# Current_Sensor.net
KiCad netlist of a schematic drawn in Altium Designer
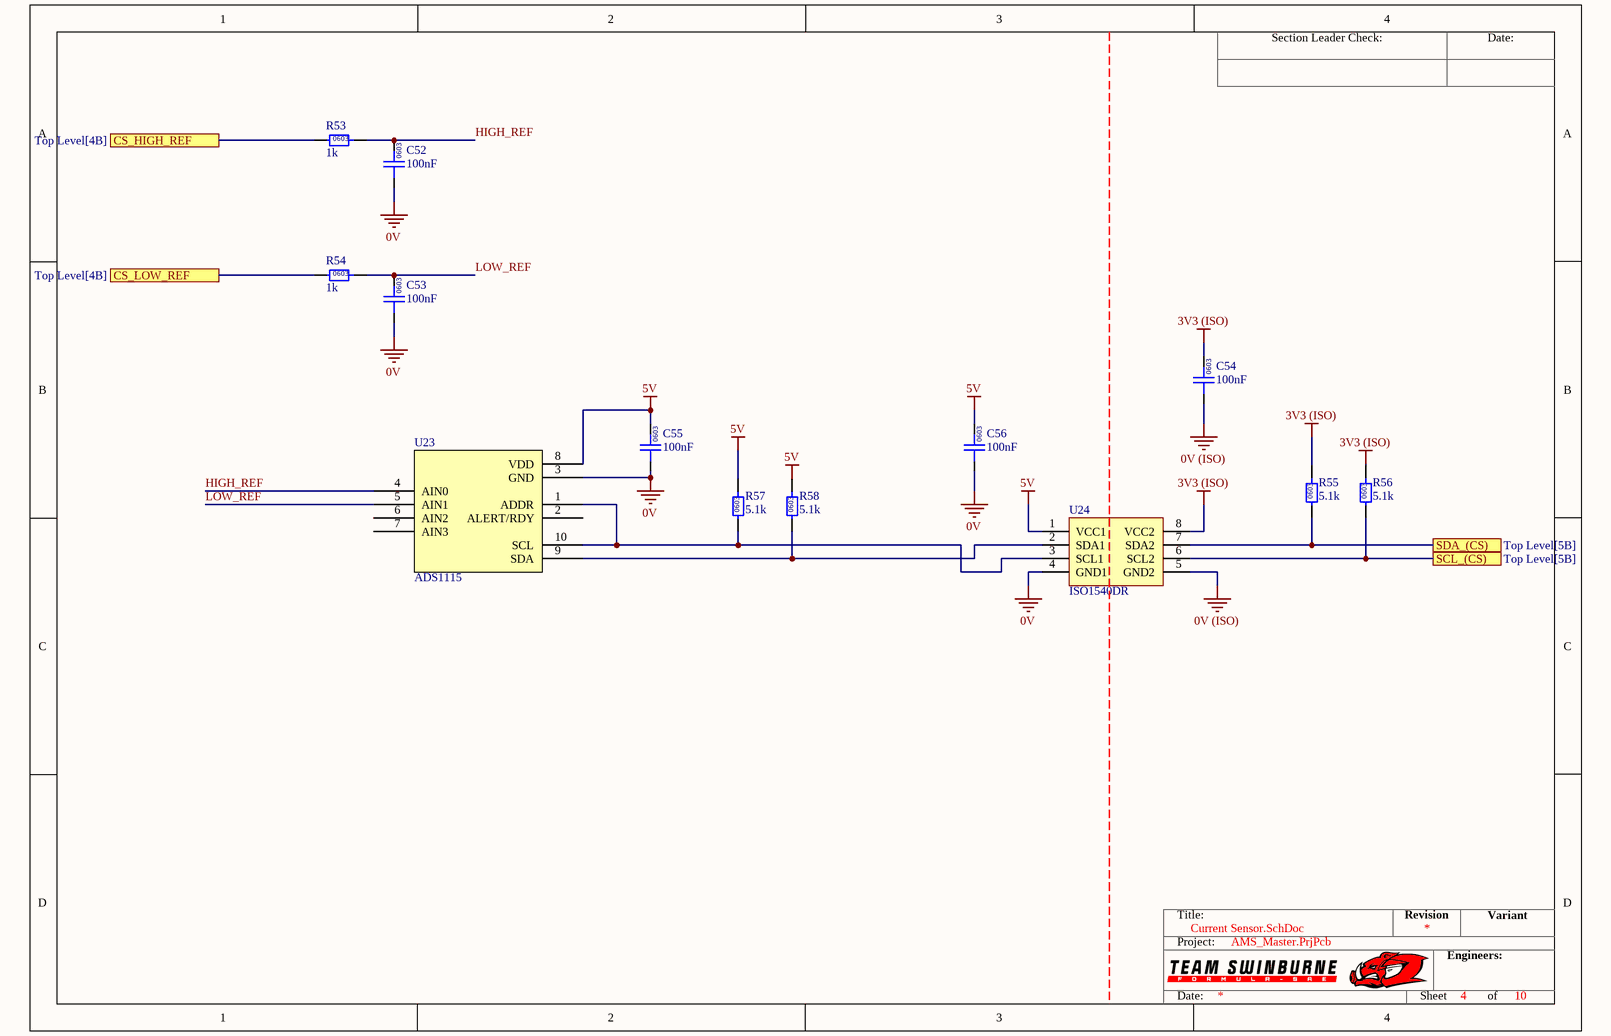
[diagram p0: Current Sensor.SchDoc]

(export (version "E")
  (design (tool "Eeschema 10.0.6"))
  (components
    (comp (ref "C52")
      (value "100nF")
      (footprint "0603")
      (fields
        (field (name "PART NUMBER") "GCM188L81H104KA57D")
        (field (name "MANUFACTURER") "muRata")
        (field (name "TOLERANCE") "±10%")
      )
      (libsource (lib "ts_standard_library") (part "Capacitor 0603"))
    )
    (comp (ref "C53")
      (value "100nF")
      (footprint "0603")
      (fields
        (field (name "PART NUMBER") "GCM188L81H104KA57D")
        (field (name "MANUFACTURER") "muRata")
        (field (name "TOLERANCE") "±10%")
      )
      (libsource (lib "ts_standard_library") (part "Capacitor 0603"))
    )
    (comp (ref "C54")
      (value "100nF")
      (footprint "0603")
      (fields
        (field (name "PART NUMBER") "GCM188L81H104KA57D")
        (field (name "MANUFACTURER") "muRata")
        (field (name "TOLERANCE") "±10%")
      )
      (libsource (lib "ts_standard_library") (part "Capacitor 0603"))
    )
    (comp (ref "C55")
      (value "100nF")
      (footprint "0603")
      (fields
        (field (name "PART NUMBER") "GCM188L81H104KA57D")
        (field (name "MANUFACTURER") "muRata")
        (field (name "TOLERANCE") "±10%")
      )
      (libsource (lib "ts_standard_library") (part "Capacitor 0603"))
    )
    (comp (ref "C56")
      (value "100nF")
      (footprint "0603")
      (fields
        (field (name "PART NUMBER") "GCM188L81H104KA57D")
        (field (name "MANUFACTURER") "muRata")
        (field (name "TOLERANCE") "±10%")
      )
      (libsource (lib "ts_standard_library") (part "Capacitor 0603"))
    )
    (comp (ref "R53")
      (value "1k")
      (footprint "0603")
      (fields
        (field (name "PART NUMBER") "RC0603FR-071KL")
        (field (name "MANUFACTURER") "YAGEO")
        (field (name "TOLERANCE") "0.01")
      )
      (libsource (lib "ts_standard_library") (part "Resistor 0603"))
    )
    (comp (ref "R54")
      (value "1k")
      (footprint "0603")
      (fields
        (field (name "PART NUMBER") "RC0603FR-071KL")
        (field (name "MANUFACTURER") "YAGEO")
        (field (name "TOLERANCE") "0.01")
      )
      (libsource (lib "ts_standard_library") (part "Resistor 0603"))
    )
    (comp (ref "R55")
      (value "5.1k")
      (footprint "0603")
      (fields
        (field (name "PART NUMBER") "RC0603JR-075K1L")
        (field (name "MANUFACTURER") "YAGEO")
        (field (name "TOLERANCE") "0.01")
      )
      (libsource (lib "ts_standard_library") (part "Resistor 0603"))
    )
    (comp (ref "R56")
      (value "5.1k")
      (footprint "0603")
      (fields
        (field (name "PART NUMBER") "RC0603JR-075K1L")
        (field (name "MANUFACTURER") "YAGEO")
        (field (name "TOLERANCE") "0.01")
      )
      (libsource (lib "ts_standard_library") (part "Resistor 0603"))
    )
    (comp (ref "R57")
      (value "5.1k")
      (footprint "0603")
      (fields
        (field (name "PART NUMBER") "RC0603JR-075K1L")
        (field (name "MANUFACTURER") "YAGEO")
        (field (name "TOLERANCE") "0.01")
      )
      (libsource (lib "ts_standard_library") (part "Resistor 0603"))
    )
    (comp (ref "R58")
      (value "5.1k")
      (footprint "0603")
      (fields
        (field (name "PART NUMBER") "RC0603JR-075K1L")
        (field (name "MANUFACTURER") "YAGEO")
        (field (name "TOLERANCE") "0.01")
      )
      (libsource (lib "ts_standard_library") (part "Resistor 0603"))
    )
    (comp (ref "U23")
      (value "ADS1115")
      (footprint "TI 10-VSSOP")
      (description "16 Bit Analog to Digital Converter 2, 4 Input 1 Sigma-Delta 10-VSSOP")
      (fields
        (field (name "MANUFACTURER") "Texas Instruments")
        (field (name "DIGIKEY PART NUMBER") "296-38849-1-ND")
      )
      (libsource (lib "ts_standard_library") (part "ADS1115"))
    )
    (comp (ref "U24")
      (value "ISO1540DR")
      (footprint "TI 8-SOIC")
      (description "I2C Digital Isolator (Multichannel)")
      (fields
        (field (name "MANUFACTURER") "Texas Instruments")
        (field (name "DIGIKEY PART NUMBER") "296-34871-1-ND")
      )
      (libsource (lib "ts_20-standard-library") (part "ISO1540DR"))
    )
  )
  (nets
    (net (code "1") (name "/CS_HIGH_REF") (class "Default")
      (node (ref "R53") (pin "1") (pinfunction "1_1") (pintype "passive"))
    )
    (net (code "2") (name "/CS_LOW_REF") (class "Default")
      (node (ref "R54") (pin "1") (pinfunction "1_1") (pintype "passive"))
    )
    (net (code "3") (name "/HIGH_REF") (class "Default")
      (node (ref "C52") (pin "2") (pinfunction "2_2") (pintype "passive"))
      (node (ref "R53") (pin "2") (pinfunction "2_2") (pintype "passive"))
      (node (ref "U23") (pin "4") (pinfunction "AIN0_4") (pintype "passive"))
    )
    (net (code "4") (name "/LOW_REF") (class "Default")
      (node (ref "C53") (pin "2") (pinfunction "2_2") (pintype "passive"))
      (node (ref "R54") (pin "2") (pinfunction "2_2") (pintype "passive"))
      (node (ref "U23") (pin "5") (pinfunction "AIN1_5") (pintype "passive"))
    )
    (net (code "5") (name "/SCL_(CS)") (class "Default")
      (node (ref "R56") (pin "1") (pinfunction "1_1") (pintype "passive"))
      (node (ref "U24") (pin "6") (pinfunction "SCL2_6") (pintype "power_in"))
    )
    (net (code "6") (name "/SDA_(CS)") (class "Default")
      (node (ref "R55") (pin "1") (pinfunction "1_1") (pintype "passive"))
      (node (ref "U24") (pin "7") (pinfunction "SDA2_7") (pintype "power_in"))
    )
    (net (code "7") (name "0V") (class "Default")
      (node (ref "C52") (pin "1") (pinfunction "1_1") (pintype "passive"))
      (node (ref "C53") (pin "1") (pinfunction "1_1") (pintype "passive"))
      (node (ref "C55") (pin "1") (pinfunction "1_1") (pintype "passive"))
      (node (ref "C56") (pin "1") (pinfunction "1_1") (pintype "passive"))
      (node (ref "U23") (pin "3") (pinfunction "GND_3") (pintype "passive"))
      (node (ref "U24") (pin "4") (pinfunction "GND1_4") (pintype "power_in"))
    )
    (net (code "8") (name "0V (ISO)") (class "Default")
      (node (ref "C54") (pin "1") (pinfunction "1_1") (pintype "passive"))
      (node (ref "U24") (pin "5") (pinfunction "GND2_5") (pintype "power_in"))
    )
    (net (code "9") (name "3V3 (ISO)") (class "Default")
      (node (ref "C54") (pin "2") (pinfunction "2_2") (pintype "passive"))
      (node (ref "R55") (pin "2") (pinfunction "2_2") (pintype "passive"))
      (node (ref "R56") (pin "2") (pinfunction "2_2") (pintype "passive"))
      (node (ref "U24") (pin "8") (pinfunction "VCC2_8") (pintype "power_in"))
    )
    (net (code "10") (name "5V") (class "Default")
      (node (ref "C55") (pin "2") (pinfunction "2_2") (pintype "passive"))
      (node (ref "C56") (pin "2") (pinfunction "2_2") (pintype "passive"))
      (node (ref "R57") (pin "2") (pinfunction "2_2") (pintype "passive"))
      (node (ref "R58") (pin "2") (pinfunction "2_2") (pintype "passive"))
      (node (ref "U23") (pin "8") (pinfunction "VDD_8") (pintype "passive"))
      (node (ref "U24") (pin "1") (pinfunction "VCC1_1") (pintype "power_in"))
    )
    (net (code "11") (name "Net-(U23-ADDR)") (class "Default")
      (node (ref "R57") (pin "1") (pinfunction "1_1") (pintype "passive"))
      (node (ref "U23") (pin "1") (pinfunction "ADDR_1") (pintype "passive"))
      (node (ref "U23") (pin "10") (pinfunction "SCL_10") (pintype "passive"))
      (node (ref "U24") (pin "3") (pinfunction "SCL1_3") (pintype "power_in"))
    )
    (net (code "12") (name "Net-(U23-SDA)") (class "Default")
      (node (ref "R58") (pin "1") (pinfunction "1_1") (pintype "passive"))
      (node (ref "U23") (pin "9") (pinfunction "SDA_9") (pintype "passive"))
      (node (ref "U24") (pin "2") (pinfunction "SDA1_2") (pintype "power_in"))
    )
    (net (code "13") (name "unconnected-(U23-AIN2-Pad6)") (class "Default")
      (node (ref "U23") (pin "6") (pinfunction "AIN2_6") (pintype "passive"))
    )
    (net (code "14") (name "unconnected-(U23-AIN3-Pad7)") (class "Default")
      (node (ref "U23") (pin "7") (pinfunction "AIN3_7") (pintype "passive"))
    )
    (net (code "15") (name "unconnected-(U23-ALERT{slash}RDY-Pad2)") (class "Default")
      (node (ref "U23") (pin "2") (pinfunction "ALERT/RDY_2") (pintype "passive"))
    )
  )
)
